# ADCIN_Matching5GHz_forACC.net
KiCad netlist of a schematic drawn in Altium Designer
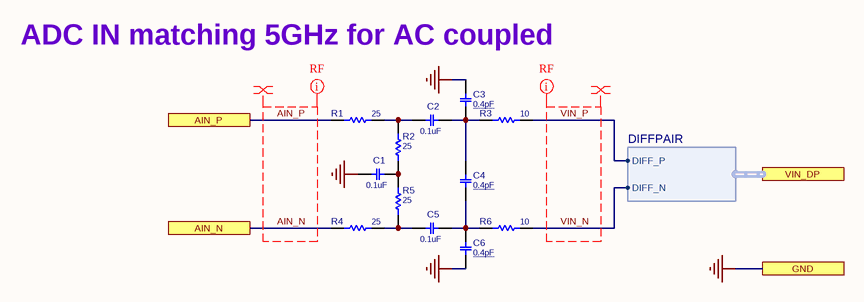
[diagram p0: ADCIN_Matching5GHz_forACC.SchDoc]

(export (version "E")
  (design (tool "Eeschema 10.0.6"))
  (components
    (comp (ref "C1")
      (value "0.1uF")
      (footprint "C0402")
      (description "CAP, MLCC")
      (libsource (lib "mlcc_smd_passive") (part "CAP_SMD_MLCC_100n50T"))
    )
    (comp (ref "C2")
      (value "0.1uF")
      (footprint "C0402")
      (description "CAP, MLCC")
      (libsource (lib "mlcc_smd_passive") (part "CAP_SMD_MLCC_100n50T"))
    )
    (comp (ref "C3")
      (value "0.4pF")
      (footprint "C0402")
      (description "CAP, MLCC")
      (libsource (lib "mlcc_smd_passive") (part "CAP_SMD_MLCC_100n50T"))
    )
    (comp (ref "C4")
      (value "0.4pF")
      (footprint "C0402")
      (description "CAP, MLCC")
      (libsource (lib "mlcc_smd_passive") (part "CAP_SMD_MLCC_100n50T"))
    )
    (comp (ref "C5")
      (value "0.1uF")
      (footprint "C0402")
      (description "CAP, MLCC")
      (libsource (lib "mlcc_smd_passive") (part "CAP_SMD_MLCC_100n50T"))
    )
    (comp (ref "C6")
      (value "0.4pF")
      (footprint "C0402")
      (description "CAP, MLCC")
      (libsource (lib "mlcc_smd_passive") (part "CAP_SMD_MLCC_100n50T"))
    )
    (comp (ref "R1")
      (value "25")
      (footprint "R0402")
      (description "RESISTOR, SMD")
      (libsource (lib "passive_res_smd") (part "RES_SMD_10K_0402"))
    )
    (comp (ref "R2")
      (value "25")
      (footprint "R0402")
      (description "RESISTOR, SMD")
      (libsource (lib "passive_res_smd") (part "RES_SMD_10K_0402"))
    )
    (comp (ref "R3")
      (value "10")
      (footprint "R0402")
      (description "RESISTOR, SMD")
      (libsource (lib "passive_res_smd") (part "RES_SMD_10K_0402"))
    )
    (comp (ref "R4")
      (value "25")
      (footprint "R0402")
      (description "RESISTOR, SMD")
      (libsource (lib "passive_res_smd") (part "RES_SMD_10K_0402"))
    )
    (comp (ref "R5")
      (value "25")
      (footprint "R0402")
      (description "RESISTOR, SMD")
      (libsource (lib "passive_res_smd") (part "RES_SMD_10K_0402"))
    )
    (comp (ref "R6")
      (value "10")
      (footprint "R0402")
      (description "RESISTOR, SMD")
      (libsource (lib "passive_res_smd") (part "RES_SMD_10K_0402"))
    )
  )
  (nets
    (net (code "2") (name "/AIN_N") (class "Default")
      (node (ref "R4") (pin "2") (pinfunction "2_2") (pintype "passive"))
    )
    (net (code "3") (name "/AIN_P") (class "Default")
      (node (ref "R1") (pin "2") (pinfunction "2_2") (pintype "passive"))
    )
    (net (code "4") (name "/VIN_N") (class "Default")
      (node (ref "R6") (pin "1") (pinfunction "1_1") (pintype "passive"))
    )
    (net (code "5") (name "/VIN_P") (class "Default")
      (node (ref "R3") (pin "1") (pinfunction "1_1") (pintype "passive"))
    )
    (net (code "7") (name "GND") (class "Default")
      (node (ref "C1") (pin "1") (pinfunction "1_1") (pintype "passive"))
      (node (ref "C3") (pin "1") (pinfunction "1_1") (pintype "passive"))
      (node (ref "C6") (pin "1") (pinfunction "1_1") (pintype "passive"))
    )
    (net (code "8") (name "Net-(C1-Pad2)") (class "Default")
      (node (ref "C1") (pin "2") (pinfunction "2_2") (pintype "passive"))
      (node (ref "R2") (pin "2") (pinfunction "2_2") (pintype "passive"))
      (node (ref "R5") (pin "1") (pinfunction "1_1") (pintype "passive"))
    )
    (net (code "9") (name "Net-(C2-Pad1)") (class "Default")
      (node (ref "C2") (pin "1") (pinfunction "1_1") (pintype "passive"))
      (node (ref "R1") (pin "1") (pinfunction "1_1") (pintype "passive"))
      (node (ref "R2") (pin "1") (pinfunction "1_1") (pintype "passive"))
    )
    (net (code "10") (name "Net-(C2-Pad2)") (class "Default")
      (node (ref "C2") (pin "2") (pinfunction "2_2") (pintype "passive"))
      (node (ref "C3") (pin "2") (pinfunction "2_2") (pintype "passive"))
      (node (ref "C4") (pin "1") (pinfunction "1_1") (pintype "passive"))
      (node (ref "R3") (pin "2") (pinfunction "2_2") (pintype "passive"))
    )
    (net (code "11") (name "Net-(C4-Pad2)") (class "Default")
      (node (ref "C4") (pin "2") (pinfunction "2_2") (pintype "passive"))
      (node (ref "C5") (pin "2") (pinfunction "2_2") (pintype "passive"))
      (node (ref "C6") (pin "2") (pinfunction "2_2") (pintype "passive"))
      (node (ref "R6") (pin "2") (pinfunction "2_2") (pintype "passive"))
    )
    (net (code "12") (name "Net-(C5-Pad1)") (class "Default")
      (node (ref "C5") (pin "1") (pinfunction "1_1") (pintype "passive"))
      (node (ref "R4") (pin "1") (pinfunction "1_1") (pintype "passive"))
      (node (ref "R5") (pin "2") (pinfunction "2_2") (pintype "passive"))
    )
  )
)
